# Relay_Board_Rev1-2_-_Altium.net
KiCad netlist of a schematic drawn in Altium Designer
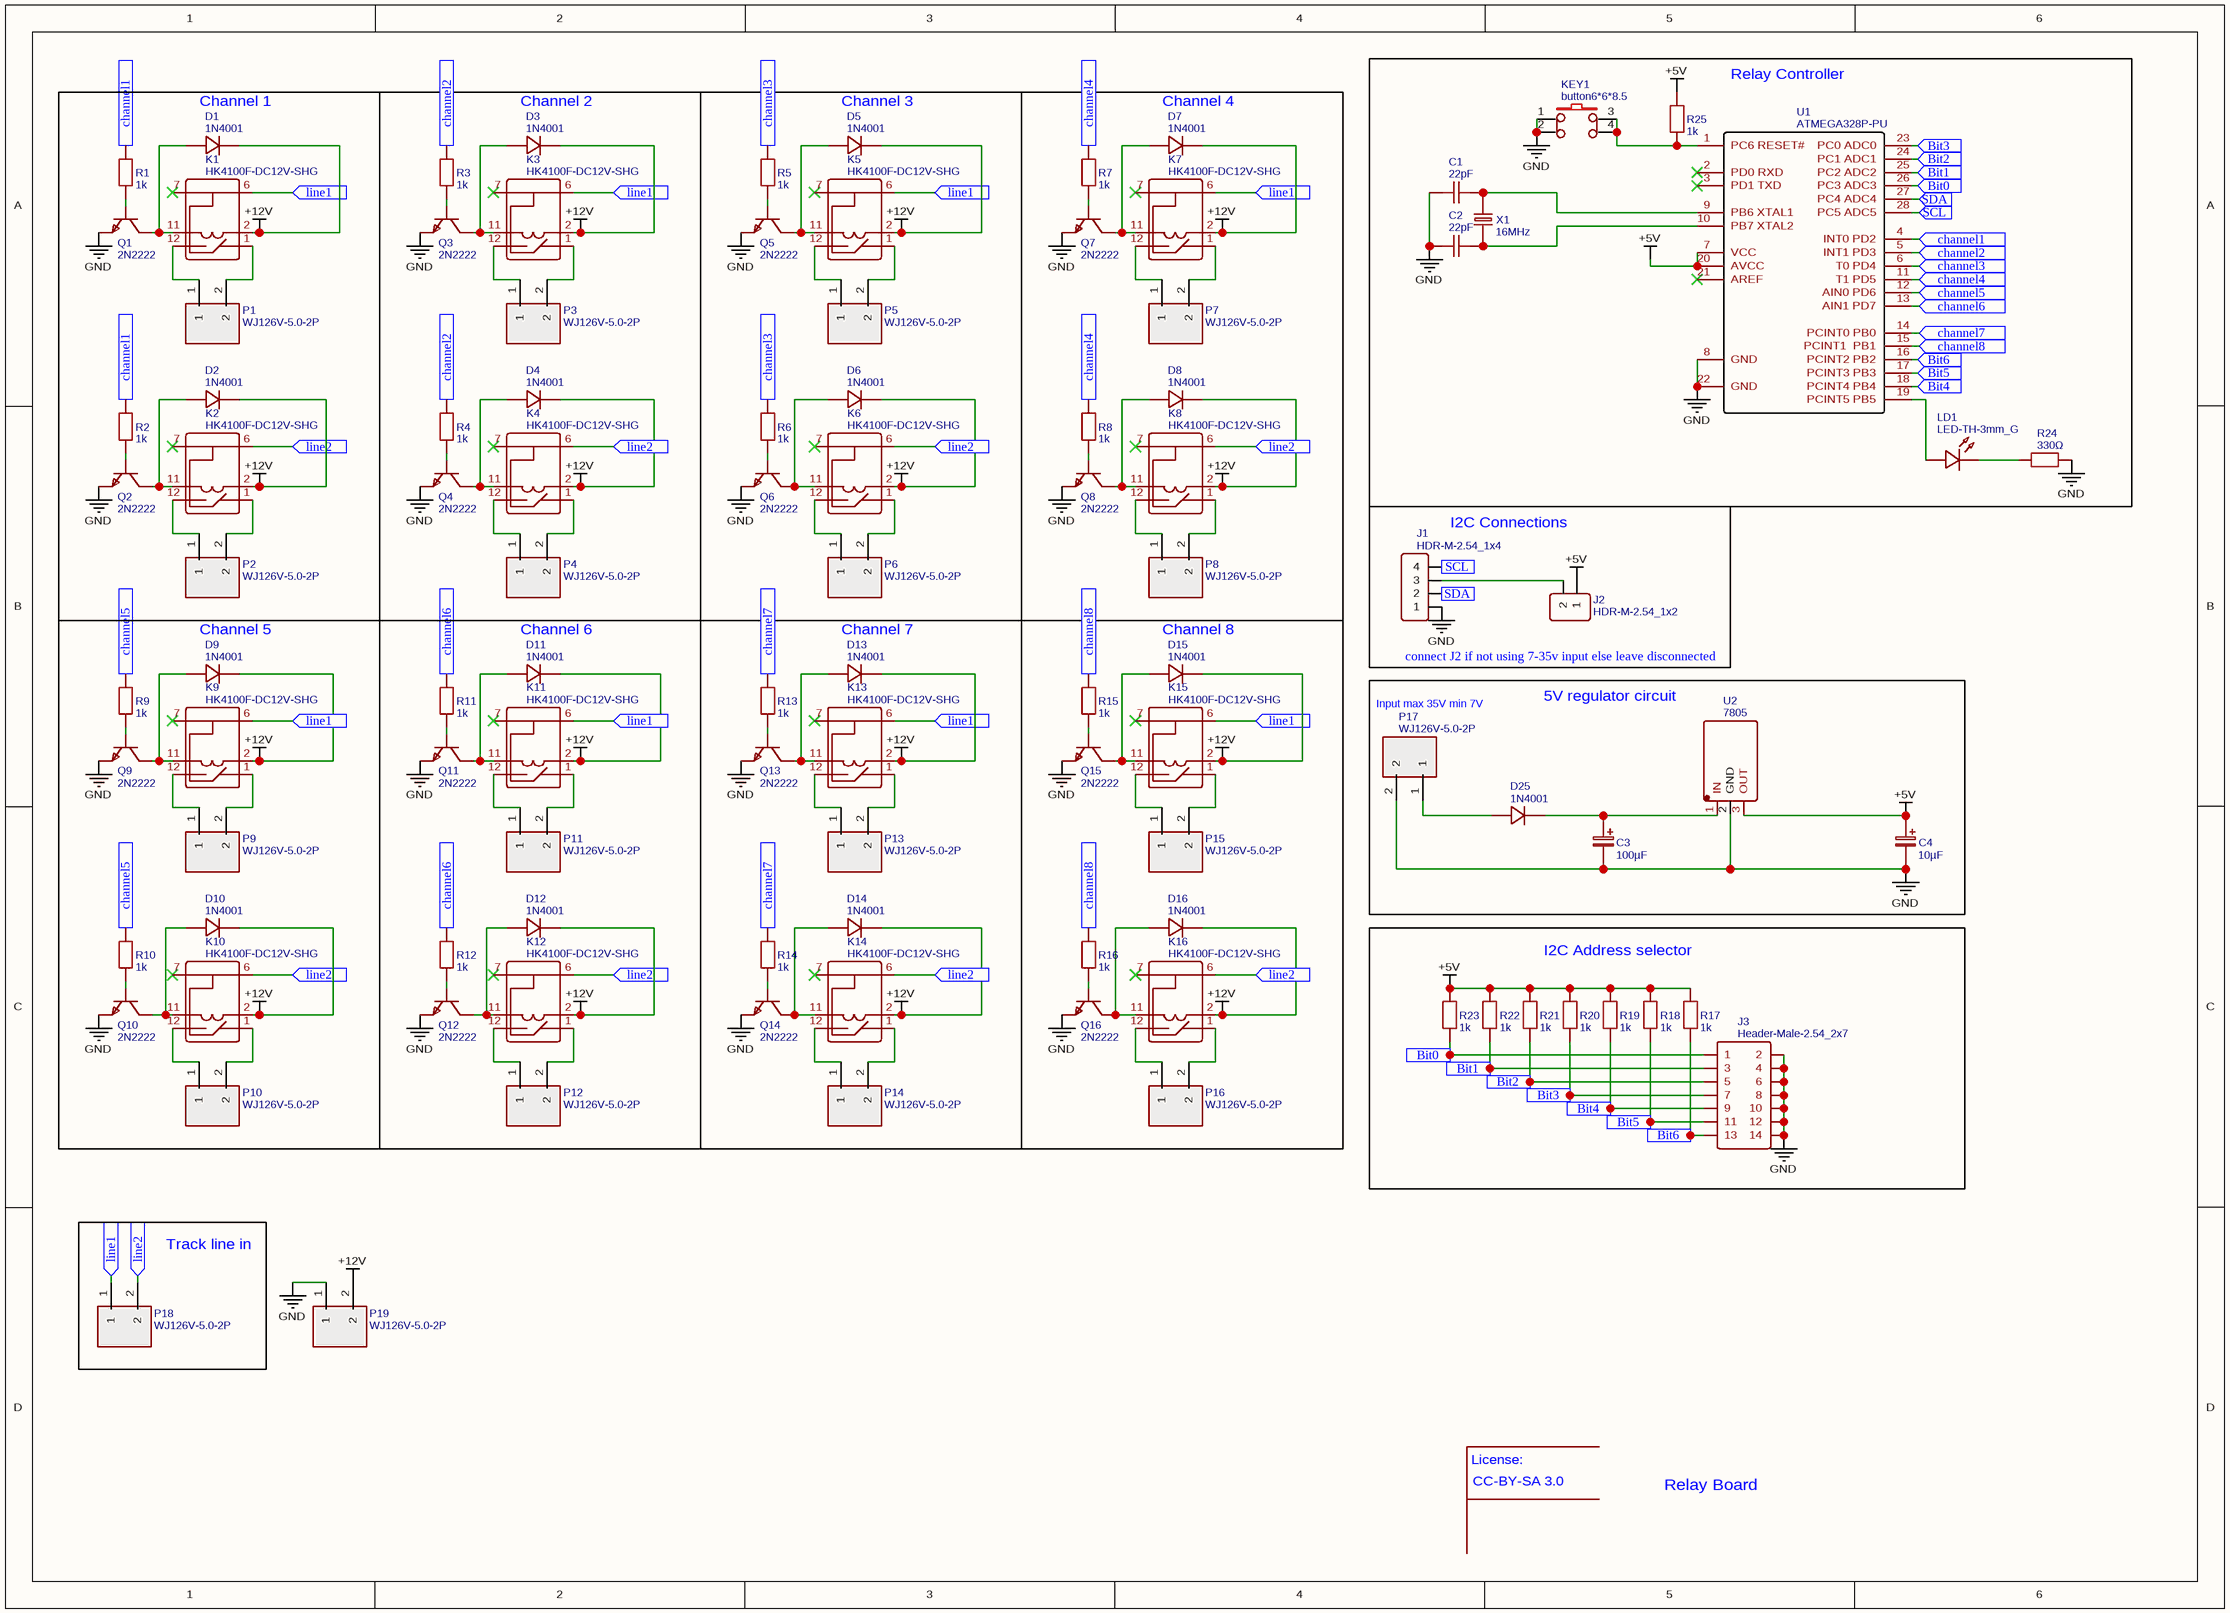
[diagram p0: Relay Board_Rev1-2 - Altium.schdoc]

(export (version "E")
  (design (tool "Eeschema 10.0.6"))
  (components
    (comp (ref "C1")
      (value "22pF")
      (fields (field (name "CONTRIBUTOR") "LCEDA_Lib"))
      (libsource (lib "altium-import") (part "root_0_22pF_"))
    )
    (comp (ref "C2")
      (value "22pF")
      (fields (field (name "CONTRIBUTOR") "LCEDA_Lib"))
      (libsource (lib "altium-import") (part "root_0_22pF_"))
    )
    (comp (ref "C3")
      (value "100µF")
      (fields (field (name "CONTRIBUTOR") "LCEDA_Lib"))
      (libsource (lib "altium-import") (part "root_3_100µF_"))
    )
    (comp (ref "C4")
      (value "10µF")
      (fields (field (name "CONTRIBUTOR") "LCEDA_Lib"))
      (libsource (lib "altium-import") (part "root_3_10µF_"))
    )
    (comp (ref "D1")
      (value "1N4001")
      (fields (field (name "BOM_SUPPLIER PART") "C82804"))
      (libsource (lib "altium-import") (part "root_2_1N4001_"))
    )
    (comp (ref "D2")
      (value "1N4001")
      (fields (field (name "BOM_SUPPLIER PART") "C82804"))
      (libsource (lib "altium-import") (part "root_2_1N4001_"))
    )
    (comp (ref "D3")
      (value "1N4001")
      (fields (field (name "BOM_SUPPLIER PART") "C82804"))
      (libsource (lib "altium-import") (part "root_2_1N4001_"))
    )
    (comp (ref "D4")
      (value "1N4001")
      (fields (field (name "BOM_SUPPLIER PART") "C82804"))
      (libsource (lib "altium-import") (part "root_2_1N4001_"))
    )
    (comp (ref "D5")
      (value "1N4001")
      (fields (field (name "BOM_SUPPLIER PART") "C82804"))
      (libsource (lib "altium-import") (part "root_2_1N4001_"))
    )
    (comp (ref "D6")
      (value "1N4001")
      (fields (field (name "BOM_SUPPLIER PART") "C82804"))
      (libsource (lib "altium-import") (part "root_2_1N4001_"))
    )
    (comp (ref "D7")
      (value "1N4001")
      (fields (field (name "BOM_SUPPLIER PART") "C82804"))
      (libsource (lib "altium-import") (part "root_2_1N4001_"))
    )
    (comp (ref "D8")
      (value "1N4001")
      (fields (field (name "BOM_SUPPLIER PART") "C82804"))
      (libsource (lib "altium-import") (part "root_2_1N4001_"))
    )
    (comp (ref "D9")
      (value "1N4001")
      (fields (field (name "BOM_SUPPLIER PART") "C82804"))
      (libsource (lib "altium-import") (part "root_2_1N4001_"))
    )
    (comp (ref "D10")
      (value "1N4001")
      (fields (field (name "BOM_SUPPLIER PART") "C82804"))
      (libsource (lib "altium-import") (part "root_2_1N4001_"))
    )
    (comp (ref "D11")
      (value "1N4001")
      (fields (field (name "BOM_SUPPLIER PART") "C82804"))
      (libsource (lib "altium-import") (part "root_2_1N4001_"))
    )
    (comp (ref "D12")
      (value "1N4001")
      (fields (field (name "BOM_SUPPLIER PART") "C82804"))
      (libsource (lib "altium-import") (part "root_2_1N4001_"))
    )
    (comp (ref "D13")
      (value "1N4001")
      (fields (field (name "BOM_SUPPLIER PART") "C82804"))
      (libsource (lib "altium-import") (part "root_2_1N4001_"))
    )
    (comp (ref "D14")
      (value "1N4001")
      (fields (field (name "BOM_SUPPLIER PART") "C82804"))
      (libsource (lib "altium-import") (part "root_2_1N4001_"))
    )
    (comp (ref "D15")
      (value "1N4001")
      (fields (field (name "BOM_SUPPLIER PART") "C82804"))
      (libsource (lib "altium-import") (part "root_2_1N4001_"))
    )
    (comp (ref "D16")
      (value "1N4001")
      (fields (field (name "BOM_SUPPLIER PART") "C82804"))
      (libsource (lib "altium-import") (part "root_2_1N4001_"))
    )
    (comp (ref "D25")
      (value "1N4001")
      (fields (field (name "BOM_SUPPLIER PART") "C82804"))
      (libsource (lib "altium-import") (part "root_2_1N4001_"))
    )
    (comp (ref "J1")
      (value "HDR-M-2.54_1x4")
      (fields (field (name "BOM_SUPPLIER PART") "C124378") (field (name "CONTRIBUTOR") "LCEDA_Lib"))
      (libsource (lib "altium-import") (part "root_2_HDR-M-2.54_1x4_"))
    )
    (comp (ref "J2")
      (value "HDR-M-2.54_1x2")
      (fields (field (name "BOM_SUPPLIER PART") "C124375") (field (name "CONTRIBUTOR") "LCEDA_Lib"))
      (libsource (lib "altium-import") (part "root_3_HDR-M-2.54_1x2_"))
    )
    (comp (ref "J3")
      (value "Header-Male-2.54_2x7")
      (fields
        (field (name "BOM_MANUFACTURER PART") "Double row of needle2X7P 2.54mm")
        (field (name "BOM_SUPPLIER PART") "C71397")
      )
      (libsource (lib "altium-import") (part "root_0_Header-Male-2.54_2x7_"))
    )
    (comp (ref "K1")
      (value "HK4100F-DC12V-SHG")
      (fields (field (name "BOM_SUPPLIER PART") "C13467"))
      (libsource (lib "altium-import") (part "root_1_HK4100F-DC12V-SHG_"))
    )
    (comp (ref "K2")
      (value "HK4100F-DC12V-SHG")
      (fields (field (name "BOM_SUPPLIER PART") "C13467"))
      (libsource (lib "altium-import") (part "root_1_HK4100F-DC12V-SHG_"))
    )
    (comp (ref "K3")
      (value "HK4100F-DC12V-SHG")
      (fields (field (name "BOM_SUPPLIER PART") "C13467"))
      (libsource (lib "altium-import") (part "root_1_HK4100F-DC12V-SHG_"))
    )
    (comp (ref "K4")
      (value "HK4100F-DC12V-SHG")
      (fields (field (name "BOM_SUPPLIER PART") "C13467"))
      (libsource (lib "altium-import") (part "root_1_HK4100F-DC12V-SHG_"))
    )
    (comp (ref "K5")
      (value "HK4100F-DC12V-SHG")
      (fields (field (name "BOM_SUPPLIER PART") "C13467"))
      (libsource (lib "altium-import") (part "root_1_HK4100F-DC12V-SHG_"))
    )
    (comp (ref "K6")
      (value "HK4100F-DC12V-SHG")
      (fields (field (name "BOM_SUPPLIER PART") "C13467"))
      (libsource (lib "altium-import") (part "root_1_HK4100F-DC12V-SHG_"))
    )
    (comp (ref "K7")
      (value "HK4100F-DC12V-SHG")
      (fields (field (name "BOM_SUPPLIER PART") "C13467"))
      (libsource (lib "altium-import") (part "root_1_HK4100F-DC12V-SHG_"))
    )
    (comp (ref "K8")
      (value "HK4100F-DC12V-SHG")
      (fields (field (name "BOM_SUPPLIER PART") "C13467"))
      (libsource (lib "altium-import") (part "root_1_HK4100F-DC12V-SHG_"))
    )
    (comp (ref "K9")
      (value "HK4100F-DC12V-SHG")
      (fields (field (name "BOM_SUPPLIER PART") "C13467"))
      (libsource (lib "altium-import") (part "root_1_HK4100F-DC12V-SHG_"))
    )
    (comp (ref "K10")
      (value "HK4100F-DC12V-SHG")
      (fields (field (name "BOM_SUPPLIER PART") "C13467"))
      (libsource (lib "altium-import") (part "root_1_HK4100F-DC12V-SHG_"))
    )
    (comp (ref "K11")
      (value "HK4100F-DC12V-SHG")
      (fields (field (name "BOM_SUPPLIER PART") "C13467"))
      (libsource (lib "altium-import") (part "root_1_HK4100F-DC12V-SHG_"))
    )
    (comp (ref "K12")
      (value "HK4100F-DC12V-SHG")
      (fields (field (name "BOM_SUPPLIER PART") "C13467"))
      (libsource (lib "altium-import") (part "root_1_HK4100F-DC12V-SHG_"))
    )
    (comp (ref "K13")
      (value "HK4100F-DC12V-SHG")
      (fields (field (name "BOM_SUPPLIER PART") "C13467"))
      (libsource (lib "altium-import") (part "root_1_HK4100F-DC12V-SHG_"))
    )
    (comp (ref "K14")
      (value "HK4100F-DC12V-SHG")
      (fields (field (name "BOM_SUPPLIER PART") "C13467"))
      (libsource (lib "altium-import") (part "root_1_HK4100F-DC12V-SHG_"))
    )
    (comp (ref "K15")
      (value "HK4100F-DC12V-SHG")
      (fields (field (name "BOM_SUPPLIER PART") "C13467"))
      (libsource (lib "altium-import") (part "root_1_HK4100F-DC12V-SHG_"))
    )
    (comp (ref "K16")
      (value "HK4100F-DC12V-SHG")
      (fields (field (name "BOM_SUPPLIER PART") "C13467"))
      (libsource (lib "altium-import") (part "root_1_HK4100F-DC12V-SHG_"))
    )
    (comp (ref "KEY1")
      (value "button6*6*8.5")
      (fields (field (name "BOM_SUPPLIER PART") "C59980"))
      (libsource (lib "altium-import") (part "root_0_button6*6*8.5_"))
    )
    (comp (ref "LD1")
      (value "LED-TH-3mm_G")
      (fields
        (field (name "BOM_MANUFACTURER PART") "204-10SYGD/S530-E3")
        (field (name "BOM_SUPPLIER PART") "C85161")
        (field (name "CONTRIBUTOR") "LCEDA_Lib")
      )
      (libsource (lib "altium-import") (part "root_0_LED-TH-3mm_G_"))
    )
    (comp (ref "P1")
      (value "WJ126V-5.0-2P")
      (fields (field (name "BOM_SUPPLIER PART") "C8404"))
      (libsource (lib "altium-import") (part "root_1_WJ126V-5.0-2P_"))
    )
    (comp (ref "P2")
      (value "WJ126V-5.0-2P")
      (fields (field (name "BOM_SUPPLIER PART") "C8404"))
      (libsource (lib "altium-import") (part "root_1_WJ126V-5.0-2P_"))
    )
    (comp (ref "P3")
      (value "WJ126V-5.0-2P")
      (fields (field (name "BOM_SUPPLIER PART") "C8404"))
      (libsource (lib "altium-import") (part "root_1_WJ126V-5.0-2P_"))
    )
    (comp (ref "P4")
      (value "WJ126V-5.0-2P")
      (fields (field (name "BOM_SUPPLIER PART") "C8404"))
      (libsource (lib "altium-import") (part "root_1_WJ126V-5.0-2P_"))
    )
    (comp (ref "P5")
      (value "WJ126V-5.0-2P")
      (fields (field (name "BOM_SUPPLIER PART") "C8404"))
      (libsource (lib "altium-import") (part "root_1_WJ126V-5.0-2P_"))
    )
    (comp (ref "P6")
      (value "WJ126V-5.0-2P")
      (fields (field (name "BOM_SUPPLIER PART") "C8404"))
      (libsource (lib "altium-import") (part "root_1_WJ126V-5.0-2P_"))
    )
    (comp (ref "P7")
      (value "WJ126V-5.0-2P")
      (fields (field (name "BOM_SUPPLIER PART") "C8404"))
      (libsource (lib "altium-import") (part "root_1_WJ126V-5.0-2P_"))
    )
    (comp (ref "P8")
      (value "WJ126V-5.0-2P")
      (fields (field (name "BOM_SUPPLIER PART") "C8404"))
      (libsource (lib "altium-import") (part "root_1_WJ126V-5.0-2P_"))
    )
    (comp (ref "P9")
      (value "WJ126V-5.0-2P")
      (fields (field (name "BOM_SUPPLIER PART") "C8404"))
      (libsource (lib "altium-import") (part "root_1_WJ126V-5.0-2P_"))
    )
    (comp (ref "P10")
      (value "WJ126V-5.0-2P")
      (fields (field (name "BOM_SUPPLIER PART") "C8404"))
      (libsource (lib "altium-import") (part "root_1_WJ126V-5.0-2P_"))
    )
    (comp (ref "P11")
      (value "WJ126V-5.0-2P")
      (fields (field (name "BOM_SUPPLIER PART") "C8404"))
      (libsource (lib "altium-import") (part "root_1_WJ126V-5.0-2P_"))
    )
    (comp (ref "P12")
      (value "WJ126V-5.0-2P")
      (fields (field (name "BOM_SUPPLIER PART") "C8404"))
      (libsource (lib "altium-import") (part "root_1_WJ126V-5.0-2P_"))
    )
    (comp (ref "P13")
      (value "WJ126V-5.0-2P")
      (fields (field (name "BOM_SUPPLIER PART") "C8404"))
      (libsource (lib "altium-import") (part "root_1_WJ126V-5.0-2P_"))
    )
    (comp (ref "P14")
      (value "WJ126V-5.0-2P")
      (fields (field (name "BOM_SUPPLIER PART") "C8404"))
      (libsource (lib "altium-import") (part "root_1_WJ126V-5.0-2P_"))
    )
    (comp (ref "P15")
      (value "WJ126V-5.0-2P")
      (fields (field (name "BOM_SUPPLIER PART") "C8404"))
      (libsource (lib "altium-import") (part "root_1_WJ126V-5.0-2P_"))
    )
    (comp (ref "P16")
      (value "WJ126V-5.0-2P")
      (fields (field (name "BOM_SUPPLIER PART") "C8404"))
      (libsource (lib "altium-import") (part "root_1_WJ126V-5.0-2P_"))
    )
    (comp (ref "P17")
      (value "WJ126V-5.0-2P")
      (fields (field (name "BOM_SUPPLIER PART") "C8404"))
      (libsource (lib "altium-import") (part "root_3_WJ126V-5.0-2P_"))
    )
    (comp (ref "P18")
      (value "WJ126V-5.0-2P")
      (fields (field (name "BOM_SUPPLIER PART") "C8404"))
      (libsource (lib "altium-import") (part "root_1_WJ126V-5.0-2P_"))
    )
    (comp (ref "P19")
      (value "WJ126V-5.0-2P")
      (fields (field (name "BOM_SUPPLIER PART") "C8404"))
      (libsource (lib "altium-import") (part "root_1_WJ126V-5.0-2P_"))
    )
    (comp (ref "Q1")
      (value "2N2222")
      (fields (field (name "BOM_SUPPLIER PART") "C118536") (field (name "CONTRIBUTOR") "LCSC"))
      (libsource (lib "altium-import") (part "root_3_2N2222_"))
    )
    (comp (ref "Q2")
      (value "2N2222")
      (fields (field (name "BOM_SUPPLIER PART") "C118536") (field (name "CONTRIBUTOR") "LCSC"))
      (libsource (lib "altium-import") (part "root_3_2N2222_"))
    )
    (comp (ref "Q3")
      (value "2N2222")
      (fields (field (name "BOM_SUPPLIER PART") "C118536") (field (name "CONTRIBUTOR") "LCSC"))
      (libsource (lib "altium-import") (part "root_3_2N2222_"))
    )
    (comp (ref "Q4")
      (value "2N2222")
      (fields (field (name "BOM_SUPPLIER PART") "C118536") (field (name "CONTRIBUTOR") "LCSC"))
      (libsource (lib "altium-import") (part "root_3_2N2222_"))
    )
    (comp (ref "Q5")
      (value "2N2222")
      (fields (field (name "BOM_SUPPLIER PART") "C118536") (field (name "CONTRIBUTOR") "LCSC"))
      (libsource (lib "altium-import") (part "root_3_2N2222_"))
    )
    (comp (ref "Q6")
      (value "2N2222")
      (fields (field (name "BOM_SUPPLIER PART") "C118536") (field (name "CONTRIBUTOR") "LCSC"))
      (libsource (lib "altium-import") (part "root_3_2N2222_"))
    )
    (comp (ref "Q7")
      (value "2N2222")
      (fields (field (name "BOM_SUPPLIER PART") "C118536") (field (name "CONTRIBUTOR") "LCSC"))
      (libsource (lib "altium-import") (part "root_3_2N2222_"))
    )
    (comp (ref "Q8")
      (value "2N2222")
      (fields (field (name "BOM_SUPPLIER PART") "C118536") (field (name "CONTRIBUTOR") "LCSC"))
      (libsource (lib "altium-import") (part "root_3_2N2222_"))
    )
    (comp (ref "Q9")
      (value "2N2222")
      (fields (field (name "BOM_SUPPLIER PART") "C118536") (field (name "CONTRIBUTOR") "LCSC"))
      (libsource (lib "altium-import") (part "root_3_2N2222_"))
    )
    (comp (ref "Q10")
      (value "2N2222")
      (fields (field (name "BOM_SUPPLIER PART") "C118536") (field (name "CONTRIBUTOR") "LCSC"))
      (libsource (lib "altium-import") (part "root_3_2N2222_"))
    )
    (comp (ref "Q11")
      (value "2N2222")
      (fields (field (name "BOM_SUPPLIER PART") "C118536") (field (name "CONTRIBUTOR") "LCSC"))
      (libsource (lib "altium-import") (part "root_3_2N2222_"))
    )
    (comp (ref "Q12")
      (value "2N2222")
      (fields (field (name "BOM_SUPPLIER PART") "C118536") (field (name "CONTRIBUTOR") "LCSC"))
      (libsource (lib "altium-import") (part "root_3_2N2222_"))
    )
    (comp (ref "Q13")
      (value "2N2222")
      (fields (field (name "BOM_SUPPLIER PART") "C118536") (field (name "CONTRIBUTOR") "LCSC"))
      (libsource (lib "altium-import") (part "root_3_2N2222_"))
    )
    (comp (ref "Q14")
      (value "2N2222")
      (fields (field (name "BOM_SUPPLIER PART") "C118536") (field (name "CONTRIBUTOR") "LCSC"))
      (libsource (lib "altium-import") (part "root_3_2N2222_"))
    )
    (comp (ref "Q15")
      (value "2N2222")
      (fields (field (name "BOM_SUPPLIER PART") "C118536") (field (name "CONTRIBUTOR") "LCSC"))
      (libsource (lib "altium-import") (part "root_3_2N2222_"))
    )
    (comp (ref "Q16")
      (value "2N2222")
      (fields (field (name "BOM_SUPPLIER PART") "C118536") (field (name "CONTRIBUTOR") "LCSC"))
      (libsource (lib "altium-import") (part "root_3_2N2222_"))
    )
    (comp (ref "R1")
      (value "1k")
      (fields (field (name "CONTRIBUTOR") "LCEDA_Lib"))
      (libsource (lib "altium-import") (part "root_1_1k_"))
    )
    (comp (ref "R2")
      (value "1k")
      (fields (field (name "CONTRIBUTOR") "LCEDA_Lib"))
      (libsource (lib "altium-import") (part "root_1_1k_"))
    )
    (comp (ref "R3")
      (value "1k")
      (fields (field (name "CONTRIBUTOR") "LCEDA_Lib"))
      (libsource (lib "altium-import") (part "root_1_1k_"))
    )
    (comp (ref "R4")
      (value "1k")
      (fields (field (name "CONTRIBUTOR") "LCEDA_Lib"))
      (libsource (lib "altium-import") (part "root_1_1k_"))
    )
    (comp (ref "R5")
      (value "1k")
      (fields (field (name "CONTRIBUTOR") "LCEDA_Lib"))
      (libsource (lib "altium-import") (part "root_1_1k_"))
    )
    (comp (ref "R6")
      (value "1k")
      (fields (field (name "CONTRIBUTOR") "LCEDA_Lib"))
      (libsource (lib "altium-import") (part "root_1_1k_"))
    )
    (comp (ref "R7")
      (value "1k")
      (fields (field (name "CONTRIBUTOR") "LCEDA_Lib"))
      (libsource (lib "altium-import") (part "root_1_1k_"))
    )
    (comp (ref "R8")
      (value "1k")
      (fields (field (name "CONTRIBUTOR") "LCEDA_Lib"))
      (libsource (lib "altium-import") (part "root_1_1k_"))
    )
    (comp (ref "R9")
      (value "1k")
      (fields (field (name "CONTRIBUTOR") "LCEDA_Lib"))
      (libsource (lib "altium-import") (part "root_1_1k_"))
    )
    (comp (ref "R10")
      (value "1k")
      (fields (field (name "CONTRIBUTOR") "LCEDA_Lib"))
      (libsource (lib "altium-import") (part "root_1_1k_"))
    )
    (comp (ref "R11")
      (value "1k")
      (fields (field (name "CONTRIBUTOR") "LCEDA_Lib"))
      (libsource (lib "altium-import") (part "root_1_1k_"))
    )
    (comp (ref "R12")
      (value "1k")
      (fields (field (name "CONTRIBUTOR") "LCEDA_Lib"))
      (libsource (lib "altium-import") (part "root_1_1k_"))
    )
    (comp (ref "R13")
      (value "1k")
      (fields (field (name "CONTRIBUTOR") "LCEDA_Lib"))
      (libsource (lib "altium-import") (part "root_1_1k_"))
    )
    (comp (ref "R14")
      (value "1k")
      (fields (field (name "CONTRIBUTOR") "LCEDA_Lib"))
      (libsource (lib "altium-import") (part "root_1_1k_"))
    )
    (comp (ref "R15")
      (value "1k")
      (fields (field (name "CONTRIBUTOR") "LCEDA_Lib"))
      (libsource (lib "altium-import") (part "root_1_1k_"))
    )
    (comp (ref "R16")
      (value "1k")
      (fields (field (name "CONTRIBUTOR") "LCEDA_Lib"))
      (libsource (lib "altium-import") (part "root_1_1k_"))
    )
    (comp (ref "R17")
      (value "1k")
      (fields (field (name "CONTRIBUTOR") "LCEDA_Lib"))
      (libsource (lib "altium-import") (part "root_1_1k_"))
    )
    (comp (ref "R18")
      (value "1k")
      (fields (field (name "CONTRIBUTOR") "LCEDA_Lib"))
      (libsource (lib "altium-import") (part "root_1_1k_"))
    )
    (comp (ref "R19")
      (value "1k")
      (fields (field (name "CONTRIBUTOR") "LCEDA_Lib"))
      (libsource (lib "altium-import") (part "root_1_1k_"))
    )
    (comp (ref "R20")
      (value "1k")
      (fields (field (name "CONTRIBUTOR") "LCEDA_Lib"))
      (libsource (lib "altium-import") (part "root_1_1k_"))
    )
    (comp (ref "R21")
      (value "1k")
      (fields (field (name "CONTRIBUTOR") "LCEDA_Lib"))
      (libsource (lib "altium-import") (part "root_1_1k_"))
    )
    (comp (ref "R22")
      (value "1k")
      (fields (field (name "CONTRIBUTOR") "LCEDA_Lib"))
      (libsource (lib "altium-import") (part "root_1_1k_"))
    )
    (comp (ref "R23")
      (value "1k")
      (fields (field (name "CONTRIBUTOR") "LCEDA_Lib"))
      (libsource (lib "altium-import") (part "root_1_1k_"))
    )
    (comp (ref "R24")
      (value "330Ω")
      (fields (field (name "CONTRIBUTOR") "LCEDA_Lib"))
      (libsource (lib "altium-import") (part "root_0_330Ω_"))
    )
    (comp (ref "R25")
      (value "1k")
      (fields (field (name "CONTRIBUTOR") "LCEDA_Lib"))
      (libsource (lib "altium-import") (part "root_1_1k_"))
    )
    (comp (ref "U1")
      (value "ATMEGA328P-PU")
      (fields (field (name "BOM_SUPPLIER PART") "C33901") (field (name "CONTRIBUTOR") "LCSC"))
      (libsource (lib "altium-import") (part "root_0_ATMEGA328P-PU_"))
    )
    (comp (ref "U2")
      (value "7805")
      (fields (field (name "BOM_SUPPLIER PART") "C305416") (field (name "CONTRIBUTOR") "LCSC"))
      (libsource (lib "altium-import") (part "root_1_7805_"))
    )
    (comp (ref "X1")
      (value "16MHz")
      (fields
        (field (name "BOM_SUPPLIER PART") "C295075")
        (field (name "BOM_MANUFACTURER PART") "XIHCELNANF-16MHZ")
        (field (name "CONTRIBUTOR") "LCSC")
      )
      (libsource (lib "altium-import") (part "root_3_16MHz_"))
    )
  )
  (nets
    (net (code "1") (name "+5V") (class "Default")
      (node (ref "C4") (pin "1") (pinfunction "1_1") (pintype "passive"))
      (node (ref "J2") (pin "1") (pinfunction "1_1") (pintype "passive"))
      (node (ref "R17") (pin "2") (pinfunction "2_2") (pintype "passive"))
      (node (ref "R18") (pin "2") (pinfunction "2_2") (pintype "passive"))
      (node (ref "R19") (pin "2") (pinfunction "2_2") (pintype "passive"))
      (node (ref "R20") (pin "2") (pinfunction "2_2") (pintype "passive"))
      (node (ref "R21") (pin "2") (pinfunction "2_2") (pintype "passive"))
      (node (ref "R22") (pin "2") (pinfunction "2_2") (pintype "passive"))
      (node (ref "R23") (pin "2") (pinfunction "2_2") (pintype "passive"))
      (node (ref "R25") (pin "2") (pinfunction "2_2") (pintype "passive"))
      (node (ref "U1") (pin "20") (pinfunction "AVCC_20") (pintype "passive"))
      (node (ref "U1") (pin "7") (pinfunction "VCC_7") (pintype "passive"))
      (node (ref "U2") (pin "3") (pinfunction "OUT_3") (pintype "passive"))
    )
    (net (code "2") (name "+12V") (class "Default")
      (node (ref "D1") (pin "1") (pinfunction "K_1") (pintype "passive"))
      (node (ref "D10") (pin "1") (pinfunction "K_1") (pintype "passive"))
      (node (ref "D11") (pin "1") (pinfunction "K_1") (pintype "passive"))
      (node (ref "D12") (pin "1") (pinfunction "K_1") (pintype "passive"))
      (node (ref "D13") (pin "1") (pinfunction "K_1") (pintype "passive"))
      (node (ref "D14") (pin "1") (pinfunction "K_1") (pintype "passive"))
      (node (ref "D15") (pin "1") (pinfunction "K_1") (pintype "passive"))
      (node (ref "D16") (pin "1") (pinfunction "K_1") (pintype "passive"))
      (node (ref "D2") (pin "1") (pinfunction "K_1") (pintype "passive"))
      (node (ref "D3") (pin "1") (pinfunction "K_1") (pintype "passive"))
      (node (ref "D4") (pin "1") (pinfunction "K_1") (pintype "passive"))
      (node (ref "D5") (pin "1") (pinfunction "K_1") (pintype "passive"))
      (node (ref "D6") (pin "1") (pinfunction "K_1") (pintype "passive"))
      (node (ref "D7") (pin "1") (pinfunction "K_1") (pintype "passive"))
      (node (ref "D8") (pin "1") (pinfunction "K_1") (pintype "passive"))
      (node (ref "D9") (pin "1") (pinfunction "K_1") (pintype "passive"))
      (node (ref "K1") (pin "2") (pinfunction "2_2") (pintype "passive"))
      (node (ref "K10") (pin "2") (pinfunction "2_2") (pintype "passive"))
      (node (ref "K11") (pin "2") (pinfunction "2_2") (pintype "passive"))
      (node (ref "K12") (pin "2") (pinfunction "2_2") (pintype "passive"))
      (node (ref "K13") (pin "2") (pinfunction "2_2") (pintype "passive"))
      (node (ref "K14") (pin "2") (pinfunction "2_2") (pintype "passive"))
      (node (ref "K15") (pin "2") (pinfunction "2_2") (pintype "passive"))
      (node (ref "K16") (pin "2") (pinfunction "2_2") (pintype "passive"))
      (node (ref "K2") (pin "2") (pinfunction "2_2") (pintype "passive"))
      (node (ref "K3") (pin "2") (pinfunction "2_2") (pintype "passive"))
      (node (ref "K4") (pin "2") (pinfunction "2_2") (pintype "passive"))
      (node (ref "K5") (pin "2") (pinfunction "2_2") (pintype "passive"))
      (node (ref "K6") (pin "2") (pinfunction "2_2") (pintype "passive"))
      (node (ref "K7") (pin "2") (pinfunction "2_2") (pintype "passive"))
      (node (ref "K8") (pin "2") (pinfunction "2_2") (pintype "passive"))
      (node (ref "K9") (pin "2") (pinfunction "2_2") (pintype "passive"))
      (node (ref "P19") (pin "2") (pinfunction "2_2") (pintype "passive"))
    )
    (net (code "3") (name "/Bit0") (class "Default")
      (node (ref "J3") (pin "1") (pinfunction "1_1") (pintype "passive"))
      (node (ref "R23") (pin "1") (pinfunction "1_1") (pintype "passive"))
      (node (ref "U1") (pin "26") (pinfunction "PC3_ADC3_26") (pintype "passive"))
    )
    (net (code "4") (name "/Bit1") (class "Default")
      (node (ref "J3") (pin "3") (pinfunction "3_3") (pintype "passive"))
      (node (ref "R22") (pin "1") (pinfunction "1_1") (pintype "passive"))
      (node (ref "U1") (pin "25") (pinfunction "PC2_ADC2_25") (pintype "passive"))
    )
    (net (code "5") (name "/Bit2") (class "Default")
      (node (ref "J3") (pin "5") (pinfunction "5_5") (pintype "passive"))
      (node (ref "R21") (pin "1") (pinfunction "1_1") (pintype "passive"))
      (node (ref "U1") (pin "24") (pinfunction "PC1_ADC1_24") (pintype "passive"))
    )
    (net (code "6") (name "/Bit3") (class "Default")
      (node (ref "J3") (pin "7") (pinfunction "7_7") (pintype "passive"))
      (node (ref "R20") (pin "1") (pinfunction "1_1") (pintype "passive"))
      (node (ref "U1") (pin "23") (pinfunction "PC0_ADC0_23") (pintype "passive"))
    )
    (net (code "7") (name "/Bit4") (class "Default")
      (node (ref "J3") (pin "9") (pinfunction "9_9") (pintype "passive"))
      (node (ref "R19") (pin "1") (pinfunction "1_1") (pintype "passive"))
      (node (ref "U1") (pin "18") (pinfunction "PCINT4_PB4_18") (pintype "passive"))
    )
    (net (code "8") (name "/Bit5") (class "Default")
      (node (ref "J3") (pin "11") (pinfunction "11_11") (pintype "passive"))
      (node (ref "R18") (pin "1") (pinfunction "1_1") (pintype "passive"))
      (node (ref "U1") (pin "17") (pinfunction "PCINT3_PB3_17") (pintype "passive"))
    )
    (net (code "9") (name "/Bit6") (class "Default")
      (node (ref "J3") (pin "13") (pinfunction "13_13") (pintype "passive"))
      (node (ref "R17") (pin "1") (pinfunction "1_1") (pintype "passive"))
      (node (ref "U1") (pin "16") (pinfunction "PCINT2_PB2_16") (pintype "passive"))
    )
    (net (code "10") (name "/SCL") (class "Default")
      (node (ref "J1") (pin "4") (pinfunction "4_4") (pintype "passive"))
      (node (ref "U1") (pin "28") (pinfunction "PC5_ADC5_28") (pintype "passive"))
    )
    (net (code "11") (name "/SDA") (class "Default")
      (node (ref "J1") (pin "2") (pinfunction "2_2") (pintype "passive"))
      (node (ref "U1") (pin "27") (pinfunction "PC4_ADC4_27") (pintype "passive"))
    )
    (net (code "12") (name "/channel1") (class "Default")
      (node (ref "R1") (pin "2") (pinfunction "2_2") (pintype "passive"))
      (node (ref "R2") (pin "2") (pinfunction "2_2") (pintype "passive"))
      (node (ref "U1") (pin "4") (pinfunction "INT0_PD2_4") (pintype "passive"))
    )
    (net (code "13") (name "/channel2") (class "Default")
      (node (ref "R3") (pin "2") (pinfunction "2_2") (pintype "passive"))
      (node (ref "R4") (pin "2") (pinfunction "2_2") (pintype "passive"))
      (node (ref "U1") (pin "5") (pinfunction "INT1_PD3_5") (pintype "passive"))
    )
    (net (code "14") (name "/channel3") (class "Default")
      (node (ref "R5") (pin "2") (pinfunction "2_2") (pintype "passive"))
      (node (ref "R6") (pin "2") (pinfunction "2_2") (pintype "passive"))
      (node (ref "U1") (pin "6") (pinfunction "T0_PD4_6") (pintype "passive"))
    )
    (net (code "15") (name "/channel4") (class "Default")
      (node (ref "R7") (pin "2") (pinfunction "2_2") (pintype "passive"))
      (node (ref "R8") (pin "2") (pinfunction "2_2") (pintype "passive"))
      (node (ref "U1") (pin "11") (pinfunction "T1_PD5_11") (pintype "passive"))
    )
    (net (code "16") (name "/channel5") (class "Default")
      (node (ref "R10") (pin "2") (pinfunction "2_2") (pintype "passive"))
      (node (ref "R9") (pin "2") (pinfunction "2_2") (pintype "passive"))
      (node (ref "U1") (pin "12") (pinfunction "AIN0_PD6_12") (pintype "passive"))
    )
    (net (code "17") (name "/channel6") (class "Default")
      (node (ref "R11") (pin "2") (pinfunction "2_2") (pintype "passive"))
      (node (ref "R12") (pin "2") (pinfunction "2_2") (pintype "passive"))
      (node (ref "U1") (pin "13") (pinfunction "AIN1_PD7_13") (pintype "passive"))
    )
    (net (code "18") (name "/channel7") (class "Default")
      (node (ref "R13") (pin "2") (pinfunction "2_2") (pintype "passive"))
      (node (ref "R14") (pin "2") (pinfunction "2_2") (pintype "passive"))
      (node (ref "U1") (pin "14") (pinfunction "PCINT0_PB0_14") (pintype "passive"))
    )
    (net (code "19") (name "/channel8") (class "Default")
      (node (ref "R15") (pin "2") (pinfunction "2_2") (pintype "passive"))
      (node (ref "R16") (pin "2") (pinfunction "2_2") (pintype "passive"))
      (node (ref "U1") (pin "15") (pinfunction "PCINT1__PB1_15") (pintype "passive"))
    )
    (net (code "20") (name "/line1") (class "Default")
      (node (ref "K1") (pin "6") (pinfunction "6_6") (pintype "passive"))
      (node (ref "K11") (pin "6") (pinfunction "6_6") (pintype "passive"))
      (node (ref "K13") (pin "6") (pinfunction "6_6") (pintype "passive"))
      (node (ref "K15") (pin "6") (pinfunction "6_6") (pintype "passive"))
      (node (ref "K3") (pin "6") (pinfunction "6_6") (pintype "passive"))
      (node (ref "K5") (pin "6") (pinfunction "6_6") (pintype "passive"))
      (node (ref "K7") (pin "6") (pinfunction "6_6") (pintype "passive"))
      (node (ref "K9") (pin "6") (pinfunction "6_6") (pintype "passive"))
      (node (ref "P18") (pin "1") (pinfunction "1_1") (pintype "passive"))
    )
    (net (code "21") (name "/line2") (class "Default")
      (node (ref "K10") (pin "6") (pinfunction "6_6") (pintype "passive"))
      (node (ref "K12") (pin "6") (pinfunction "6_6") (pintype "passive"))
      (node (ref "K14") (pin "6") (pinfunction "6_6") (pintype "passive"))
      (node (ref "K16") (pin "6") (pinfunction "6_6") (pintype "passive"))
      (node (ref "K2") (pin "6") (pinfunction "6_6") (pintype "passive"))
      (node (ref "K4") (pin "6") (pinfunction "6_6") (pintype "passive"))
      (node (ref "K6") (pin "6") (pinfunction "6_6") (pintype "passive"))
      (node (ref "K8") (pin "6") (pinfunction "6_6") (pintype "passive"))
      (node (ref "P18") (pin "2") (pinfunction "2_2") (pintype "passive"))
    )
    (net (code "22") (name "GND") (class "Default")
      (node (ref "C1") (pin "1") (pinfunction "1_1") (pintype "passive"))
      (node (ref "C2") (pin "1") (pinfunction "1_1") (pintype "passive"))
      (node (ref "C3") (pin "2") (pinfunction "2_2") (pintype "passive"))
      (node (ref "C4") (pin "2") (pinfunction "2_2") (pintype "passive"))
      (node (ref "J1") (pin "1") (pinfunction "1_1") (pintype "passive"))
      (node (ref "J3") (pin "10") (pinfunction "10_10") (pintype "passive"))
      (node (ref "J3") (pin "12") (pinfunction "12_12") (pintype "passive"))
      (node (ref "J3") (pin "14") (pinfunction "14_14") (pintype "passive"))
      (node (ref "J3") (pin "2") (pinfunction "2_2") (pintype "passive"))
      (node (ref "J3") (pin "4") (pinfunction "4_4") (pintype "passive"))
      (node (ref "J3") (pin "6") (pinfunction "6_6") (pintype "passive"))
      (node (ref "J3") (pin "8") (pinfunction "8_8") (pintype "passive"))
      (node (ref "KEY1") (pin "1") (pinfunction "1_1") (pintype "passive"))
      (node (ref "KEY1") (pin "2") (pinfunction "2_2") (pintype "passive"))
      (node (ref "P17") (pin "2") (pinfunction "2_2") (pintype "passive"))
      (node (ref "P19") (pin "1") (pinfunction "1_1") (pintype "passive"))
      (node (ref "Q1") (pin "1") (pinfunction "E_1") (pintype "passive"))
      (node (ref "Q10") (pin "1") (pinfunction "E_1") (pintype "passive"))
      (node (ref "Q11") (pin "1") (pinfunction "E_1") (pintype "passive"))
      (node (ref "Q12") (pin "1") (pinfunction "E_1") (pintype "passive"))
      (node (ref "Q13") (pin "1") (pinfunction "E_1") (pintype "passive"))
      (node (ref "Q14") (pin "1") (pinfunction "E_1") (pintype "passive"))
      (node (ref "Q15") (pin "1") (pinfunction "E_1") (pintype "passive"))
      (node (ref "Q16") (pin "1") (pinfunction "E_1") (pintype "passive"))
      (node (ref "Q2") (pin "1") (pinfunction "E_1") (pintype "passive"))
      (node (ref "Q3") (pin "1") (pinfunction "E_1") (pintype "passive"))
      (node (ref "Q4") (pin "1") (pinfunction "E_1") (pintype "passive"))
      (node (ref "Q5") (pin "1") (pinfunction "E_1") (pintype "passive"))
      (node (ref "Q6") (pin "1") (pinfunction "E_1") (pintype "passive"))
      (node (ref "Q7") (pin "1") (pinfunction "E_1") (pintype "passive"))
      (node (ref "Q8") (pin "1") (pinfunction "E_1") (pintype "passive"))
      (node (ref "Q9") (pin "1") (pinfunction "E_1") (pintype "passive"))
      (node (ref "R24") (pin "2") (pinfunction "2_2") (pintype "passive"))
      (node (ref "U1") (pin "22") (pinfunction "GND_22") (pintype "passive"))
      (node (ref "U1") (pin "8") (pinfunction "GND_8") (pintype "passive"))
      (node (ref "U2") (pin "2") (pinfunction "GND_2") (pintype "passive"))
    )
    (net (code "23") (name "Net-(D1-A)") (class "Default")
      (node (ref "D1") (pin "2") (pinfunction "A_2") (pintype "passive"))
      (node (ref "K1") (pin "11") (pinfunction "11_11") (pintype "passive"))
      (node (ref "Q1") (pin "3") (pinfunction "C_3") (pintype "passive"))
    )
    (net (code "24") (name "Net-(D2-A)") (class "Default")
      (node (ref "D2") (pin "2") (pinfunction "A_2") (pintype "passive"))
      (node (ref "K2") (pin "11") (pinfunction "11_11") (pintype "passive"))
      (node (ref "Q2") (pin "3") (pinfunction "C_3") (pintype "passive"))
    )
    (net (code "25") (name "Net-(D3-A)") (class "Default")
      (node (ref "D3") (pin "2") (pinfunction "A_2") (pintype "passive"))
      (node (ref "K3") (pin "11") (pinfunction "11_11") (pintype "passive"))
      (node (ref "Q3") (pin "3") (pinfunction "C_3") (pintype "passive"))
    )
    (net (code "26") (name "Net-(D4-A)") (class "Default")
      (node (ref "D4") (pin "2") (pinfunction "A_2") (pintype "passive"))
      (node (ref "K4") (pin "11") (pinfunction "11_11") (pintype "passive"))
      (node (ref "Q4") (pin "3") (pinfunction "C_3") (pintype "passive"))
    )
    (net (code "27") (name "Net-(D5-A)") (class "Default")
      (node (ref "D5") (pin "2") (pinfunction "A_2") (pintype "passive"))
      (node (ref "K5") (pin "11") (pinfunction "11_11") (pintype "passive"))
      (node (ref "Q5") (pin "3") (pinfunction "C_3") (pintype "passive"))
    )
    (net (code "28") (name "Net-(D6-A)") (class "Default")
      (node (ref "D6") (pin "2") (pinfunction "A_2") (pintype "passive"))
      (node (ref "K6") (pin "11") (pinfunction "11_11") (pintype "passive"))
      (node (ref "Q6") (pin "3") (pinfunction "C_3") (pintype "passive"))
    )
    (net (code "29") (name "Net-(D7-A)") (class "Default")
      (node (ref "D7") (pin "2") (pinfunction "A_2") (pintype "passive"))
      (node (ref "K7") (pin "11") (pinfunction "11_11") (pintype "passive"))
      (node (ref "Q7") (pin "3") (pinfunction "C_3") (pintype "passive"))
    )
    (net (code "30") (name "Net-(D8-A)") (class "Default")
      (node (ref "D8") (pin "2") (pinfunction "A_2") (pintype "passive"))
      (node (ref "K8") (pin "11") (pinfunction "11_11") (pintype "passive"))
      (node (ref "Q8") (pin "3") (pinfunction "C_3") (pintype "passive"))
    )
    (net (code "31") (name "Net-(D9-A)") (class "Default")
      (node (ref "D9") (pin "2") (pinfunction "A_2") (pintype "passive"))
      (node (ref "K9") (pin "11") (pinfunction "11_11") (pintype "passive"))
      (node (ref "Q9") (pin "3") (pinfunction "C_3") (pintype "passive"))
    )
    (net (code "32") (name "Net-(D10-A)") (class "Default")
      (node (ref "D10") (pin "2") (pinfunction "A_2") (pintype "passive"))
      (node (ref "K10") (pin "11") (pinfunction "11_11") (pintype "passive"))
      (node (ref "Q10") (pin "3") (pinfunction "C_3") (pintype "passive"))
    )
    (net (code "33") (name "Net-(D11-A)") (class "Default")
      (node (ref "D11") (pin "2") (pinfunction "A_2") (pintype "passive"))
      (node (ref "K11") (pin "11") (pinfunction "11_11") (pintype "passive"))
      (node (ref "Q11") (pin "3") (pinfunction "C_3") (pintype "passive"))
    )
    (net (code "34") (name "Net-(D12-A)") (class "Default")
      (node (ref "D12") (pin "2") (pinfunction "A_2") (pintype "passive"))
      (node (ref "K12") (pin "11") (pinfunction "11_11") (pintype "passive"))
      (node (ref "Q12") (pin "3") (pinfunction "C_3") (pintype "passive"))
    )
    (net (code "35") (name "Net-(D13-A)") (class "Default")
      (node (ref "D13") (pin "2") (pinfunction "A_2") (pintype "passive"))
      (node (ref "K13") (pin "11") (pinfunction "11_11") (pintype "passive"))
      (node (ref "Q13") (pin "3") (pinfunction "C_3") (pintype "passive"))
    )
    (net (code "36") (name "Net-(D14-A)") (class "Default")
      (node (ref "D14") (pin "2") (pinfunction "A_2") (pintype "passive"))
      (node (ref "K14") (pin "11") (pinfunction "11_11") (pintype "passive"))
      (node (ref "Q14") (pin "3") (pinfunction "C_3") (pintype "passive"))
    )
    (net (code "37") (name "Net-(D15-A)") (class "Default")
      (node (ref "D15") (pin "2") (pinfunction "A_2") (pintype "passive"))
      (node (ref "K15") (pin "11") (pinfunction "11_11") (pintype "passive"))
      (node (ref "Q15") (pin "3") (pinfunction "C_3") (pintype "passive"))
    )
    (net (code "38") (name "Net-(D16-A)") (class "Default")
      (node (ref "D16") (pin "2") (pinfunction "A_2") (pintype "passive"))
      (node (ref "K16") (pin "11") (pinfunction "11_11") (pintype "passive"))
      (node (ref "Q16") (pin "3") (pinfunction "C_3") (pintype "passive"))
    )
    (net (code "39") (name "Net-(D25-A)") (class "Default")
      (node (ref "D25") (pin "2") (pinfunction "A_2") (pintype "passive"))
      (node (ref "P17") (pin "1") (pinfunction "1_1") (pintype "passive"))
    )
    (net (code "40") (name "Net-(D25-K)") (class "Default")
      (node (ref "C3") (pin "1") (pinfunction "1_1") (pintype "passive"))
      (node (ref "D25") (pin "1") (pinfunction "K_1") (pintype "passive"))
      (node (ref "U2") (pin "1") (pinfunction "IN_1") (pintype "passive"))
    )
    (net (code "41") (name "Net-(J1-Pad3)") (class "Default")
      (node (ref "J1") (pin "3") (pinfunction "3_3") (pintype "passive"))
      (node (ref "J2") (pin "2") (pinfunction "2_2") (pintype "passive"))
    )
    (net (code "42") (name "Net-(K1-Pad1)") (class "Default")
      (node (ref "K1") (pin "1") (pinfunction "1_1") (pintype "passive"))
      (node (ref "P1") (pin "2") (pinfunction "2_2") (pintype "passive"))
    )
    (net (code "43") (name "Net-(K1-Pad12)") (class "Default")
      (node (ref "K1") (pin "12") (pinfunction "12_12") (pintype "passive"))
      (node (ref "P1") (pin "1") (pinfunction "1_1") (pintype "passive"))
    )
    (net (code "44") (name "Net-(K2-Pad1)") (class "Default")
      (node (ref "K2") (pin "1") (pinfunction "1_1") (pintype "passive"))
      (node (ref "P2") (pin "2") (pinfunction "2_2") (pintype "passive"))
    )
    (net (code "45") (name "Net-(K2-Pad12)") (class "Default")
      (node (ref "K2") (pin "12") (pinfunction "12_12") (pintype "passive"))
      (node (ref "P2") (pin "1") (pinfunction "1_1") (pintype "passive"))
    )
    (net (code "46") (name "Net-(K3-Pad1)") (class "Default")
      (node (ref "K3") (pin "1") (pinfunction "1_1") (pintype "passive"))
      (node (ref "P3") (pin "2") (pinfunction "2_2") (pintype "passive"))
    )
    (net (code "47") (name "Net-(K3-Pad12)") (class "Default")
      (node (ref "K3") (pin "12") (pinfunction "12_12") (pintype "passive"))
      (node (ref "P3") (pin "1") (pinfunction "1_1") (pintype "passive"))
    )
    (net (code "48") (name "Net-(K4-Pad1)") (class "Default")
      (node (ref "K4") (pin "1") (pinfunction "1_1") (pintype "passive"))
      (node (ref "P4") (pin "2") (pinfunction "2_2") (pintype "passive"))
    )
    (net (code "49") (name "Net-(K4-Pad12)") (class "Default")
      (node (ref "K4") (pin "12") (pinfunction "12_12") (pintype "passive"))
      (node (ref "P4") (pin "1") (pinfunction "1_1") (pintype "passive"))
    )
    (net (code "50") (name "Net-(K5-Pad1)") (class "Default")
      (node (ref "K5") (pin "1") (pinfunction "1_1") (pintype "passive"))
      (node (ref "P5") (pin "2") (pinfunction "2_2") (pintype "passive"))
    )
    (net (code "51") (name "Net-(K5-Pad12)") (class "Default")
      (node (ref "K5") (pin "12") (pinfunction "12_12") (pintype "passive"))
      (node (ref "P5") (pin "1") (pinfunction "1_1") (pintype "passive"))
    )
    (net (code "52") (name "Net-(K6-Pad1)") (class "Default")
      (node (ref "K6") (pin "1") (pinfunction "1_1") (pintype "passive"))
      (node (ref "P6") (pin "2") (pinfunction "2_2") (pintype "passive"))
    )
    (net (code "53") (name "Net-(K6-Pad12)") (class "Default")
      (node (ref "K6") (pin "12") (pinfunction "12_12") (pintype "passive"))
      (node (ref "P6") (pin "1") (pinfunction "1_1") (pintype "passive"))
    )
    (net (code "54") (name "Net-(K7-Pad1)") (class "Default")
      (node (ref "K7") (pin "1") (pinfunction "1_1") (pintype "passive"))
      (node (ref "P7") (pin "2") (pinfunction "2_2") (pintype "passive"))
    )
    (net (code "55") (name "Net-(K7-Pad12)") (class "Default")
      (node (ref "K7") (pin "12") (pinfunction "12_12") (pintype "passive"))
      (node (ref "P7") (pin "1") (pinfunction "1_1") (pintype "passive"))
    )
    (net (code "56") (name "Net-(K8-Pad1)") (class "Default")
      (node (ref "K8") (pin "1") (pinfunction "1_1") (pintype "passive"))
      (node (ref "P8") (pin "2") (pinfunction "2_2") (pintype "passive"))
    )
    (net (code "57") (name "Net-(K8-Pad12)") (class "Default")
      (node (ref "K8") (pin "12") (pinfunction "12_12") (pintype "passive"))
      (node (ref "P8") (pin "1") (pinfunction "1_1") (pintype "passive"))
    )
    (net (code "58") (name "Net-(K9-Pad1)") (class "Default")
      (node (ref "K9") (pin "1") (pinfunction "1_1") (pintype "passive"))
      (node (ref "P9") (pin "2") (pinfunction "2_2") (pintype "passive"))
    )
    (net (code "59") (name "Net-(K9-Pad12)") (class "Default")
      (node (ref "K9") (pin "12") (pinfunction "12_12") (pintype "passive"))
      (node (ref "P9") (pin "1") (pinfunction "1_1") (pintype "passive"))
    )
    (net (code "60") (name "Net-(K10-Pad1)") (class "Default")
      (node (ref "K10") (pin "1") (pinfunction "1_1") (pintype "passive"))
      (node (ref "P10") (pin "2") (pinfunction "2_2") (pintype "passive"))
    )
    (net (code "61") (name "Net-(K10-Pad12)") (class "Default")
      (node (ref "K10") (pin "12") (pinfunction "12_12") (pintype "passive"))
      (node (ref "P10") (pin "1") (pinfunction "1_1") (pintype "passive"))
    )
    (net (code "62") (name "Net-(K11-Pad1)") (class "Default")
      (node (ref "K11") (pin "1") (pinfunction "1_1") (pintype "passive"))
      (node (ref "P11") (pin "2") (pinfunction "2_2") (pintype "passive"))
    )
    (net (code "63") (name "Net-(K11-Pad12)") (class "Default")
      (node (ref "K11") (pin "12") (pinfunction "12_12") (pintype "passive"))
      (node (ref "P11") (pin "1") (pinfunction "1_1") (pintype "passive"))
    )
    (net (code "64") (name "Net-(K12-Pad1)") (class "Default")
      (node (ref "K12") (pin "1") (pinfunction "1_1") (pintype "passive"))
      (node (ref "P12") (pin "2") (pinfunction "2_2") (pintype "passive"))
    )
    (net (code "65") (name "Net-(K12-Pad12)") (class "Default")
      (node (ref "K12") (pin "12") (pinfunction "12_12") (pintype "passive"))
      (node (ref "P12") (pin "1") (pinfunction "1_1") (pintype "passive"))
    )
    (net (code "66") (name "Net-(K13-Pad1)") (class "Default")
      (node (ref "K13") (pin "1") (pinfunction "1_1") (pintype "passive"))
      (node (ref "P13") (pin "2") (pinfunction "2_2") (pintype "passive"))
    )
    (net (code "67") (name "Net-(K13-Pad12)") (class "Default")
      (node (ref "K13") (pin "12") (pinfunction "12_12") (pintype "passive"))
      (node (ref "P13") (pin "1") (pinfunction "1_1") (pintype "passive"))
    )
    (net (code "68") (name "Net-(K14-Pad1)") (class "Default")
      (node (ref "K14") (pin "1") (pinfunction "1_1") (pintype "passive"))
      (node (ref "P14") (pin "2") (pinfunction "2_2") (pintype "passive"))
    )
    (net (code "69") (name "Net-(K14-Pad12)") (class "Default")
      (node (ref "K14") (pin "12") (pinfunction "12_12") (pintype "passive"))
      (node (ref "P14") (pin "1") (pinfunction "1_1") (pintype "passive"))
    )
    (net (code "70") (name "Net-(K15-Pad1)") (class "Default")
      (node (ref "K15") (pin "1") (pinfunction "1_1") (pintype "passive"))
      (node (ref "P15") (pin "2") (pinfunction "2_2") (pintype "passive"))
    )
    (net (code "71") (name "Net-(K15-Pad12)") (class "Default")
      (node (ref "K15") (pin "12") (pinfunction "12_12") (pintype "passive"))
      (node (ref "P15") (pin "1") (pinfunction "1_1") (pintype "passive"))
    )
    (net (code "72") (name "Net-(K16-Pad1)") (class "Default")
      (node (ref "K16") (pin "1") (pinfunction "1_1") (pintype "passive"))
      (node (ref "P16") (pin "2") (pinfunction "2_2") (pintype "passive"))
    )
    (net (code "73") (name "Net-(K16-Pad12)") (class "Default")
      (node (ref "K16") (pin "12") (pinfunction "12_12") (pintype "passive"))
      (node (ref "P16") (pin "1") (pinfunction "1_1") (pintype "passive"))
    )
    (net (code "74") (name "Net-(LD1-Pad2)") (class "Default")
      (node (ref "LD1") (pin "2") (pinfunction "2_2") (pintype "passive"))
      (node (ref "R24") (pin "1") (pinfunction "1_1") (pintype "passive"))
    )
    (net (code "75") (name "Net-(Q1-B)") (class "Default")
      (node (ref "Q1") (pin "2") (pinfunction "B_2") (pintype "passive"))
      (node (ref "R1") (pin "1") (pinfunction "1_1") (pintype "passive"))
    )
    (net (code "76") (name "Net-(Q2-B)") (class "Default")
      (node (ref "Q2") (pin "2") (pinfunction "B_2") (pintype "passive"))
      (node (ref "R2") (pin "1") (pinfunction "1_1") (pintype "passive"))
    )
    (net (code "77") (name "Net-(Q3-B)") (class "Default")
      (node (ref "Q3") (pin "2") (pinfunction "B_2") (pintype "passive"))
      (node (ref "R3") (pin "1") (pinfunction "1_1") (pintype "passive"))
    )
    (net (code "78") (name "Net-(Q4-B)") (class "Default")
      (node (ref "Q4") (pin "2") (pinfunction "B_2") (pintype "passive"))
      (node (ref "R4") (pin "1") (pinfunction "1_1") (pintype "passive"))
    )
    (net (code "79") (name "Net-(Q5-B)") (class "Default")
      (node (ref "Q5") (pin "2") (pinfunction "B_2") (pintype "passive"))
      (node (ref "R5") (pin "1") (pinfunction "1_1") (pintype "passive"))
    )
    (net (code "80") (name "Net-(Q6-B)") (class "Default")
      (node (ref "Q6") (pin "2") (pinfunction "B_2") (pintype "passive"))
      (node (ref "R6") (pin "1") (pinfunction "1_1") (pintype "passive"))
    )
    (net (code "81") (name "Net-(Q7-B)") (class "Default")
      (node (ref "Q7") (pin "2") (pinfunction "B_2") (pintype "passive"))
      (node (ref "R7") (pin "1") (pinfunction "1_1") (pintype "passive"))
    )
    (net (code "82") (name "Net-(Q8-B)") (class "Default")
      (node (ref "Q8") (pin "2") (pinfunction "B_2") (pintype "passive"))
      (node (ref "R8") (pin "1") (pinfunction "1_1") (pintype "passive"))
    )
    (net (code "83") (name "Net-(Q9-B)") (class "Default")
      (node (ref "Q9") (pin "2") (pinfunction "B_2") (pintype "passive"))
      (node (ref "R9") (pin "1") (pinfunction "1_1") (pintype "passive"))
    )
    (net (code "84") (name "Net-(Q10-B)") (class "Default")
      (node (ref "Q10") (pin "2") (pinfunction "B_2") (pintype "passive"))
      (node (ref "R10") (pin "1") (pinfunction "1_1") (pintype "passive"))
    )
    (net (code "85") (name "Net-(Q11-B)") (class "Default")
      (node (ref "Q11") (pin "2") (pinfunction "B_2") (pintype "passive"))
      (node (ref "R11") (pin "1") (pinfunction "1_1") (pintype "passive"))
    )
    (net (code "86") (name "Net-(Q12-B)") (class "Default")
      (node (ref "Q12") (pin "2") (pinfunction "B_2") (pintype "passive"))
      (node (ref "R12") (pin "1") (pinfunction "1_1") (pintype "passive"))
    )
    (net (code "87") (name "Net-(Q13-B)") (class "Default")
      (node (ref "Q13") (pin "2") (pinfunction "B_2") (pintype "passive"))
      (node (ref "R13") (pin "1") (pinfunction "1_1") (pintype "passive"))
    )
    (net (code "88") (name "Net-(Q14-B)") (class "Default")
      (node (ref "Q14") (pin "2") (pinfunction "B_2") (pintype "passive"))
      (node (ref "R14") (pin "1") (pinfunction "1_1") (pintype "passive"))
    )
    (net (code "89") (name "Net-(Q15-B)") (class "Default")
      (node (ref "Q15") (pin "2") (pinfunction "B_2") (pintype "passive"))
      (node (ref "R15") (pin "1") (pinfunction "1_1") (pintype "passive"))
    )
    (net (code "90") (name "Net-(Q16-B)") (class "Default")
      (node (ref "Q16") (pin "2") (pinfunction "B_2") (pintype "passive"))
      (node (ref "R16") (pin "1") (pinfunction "1_1") (pintype "passive"))
    )
    (net (code "91") (name "Net-(U1-PB6_XTAL1)") (class "Default")
      (node (ref "C1") (pin "2") (pinfunction "2_2") (pintype "passive"))
      (node (ref "U1") (pin "9") (pinfunction "PB6_XTAL1_9") (pintype "passive"))
      (node (ref "X1") (pin "1") (pinfunction "1_1") (pintype "passive"))
    )
    (net (code "92") (name "Net-(U1-PB7_XTAL2)") (class "Default")
      (node (ref "C2") (pin "2") (pinfunction "2_2") (pintype "passive"))
      (node (ref "U1") (pin "10") (pinfunction "PB7_XTAL2_10") (pintype "passive"))
      (node (ref "X1") (pin "2") (pinfunction "2_2") (pintype "passive"))
    )
    (net (code "93") (name "Net-(U1-PC6_RESET#)") (class "Default")
      (node (ref "KEY1") (pin "3") (pinfunction "3_3") (pintype "passive"))
      (node (ref "KEY1") (pin "4") (pinfunction "4_4") (pintype "passive"))
      (node (ref "R25") (pin "1") (pinfunction "1_1") (pintype "passive"))
      (node (ref "U1") (pin "1") (pinfunction "PC6_RESET#_1") (pintype "passive"))
    )
    (net (code "94") (name "Net-(U1-PCINT5_PB5)") (class "Default")
      (node (ref "LD1") (pin "1") (pinfunction "1_1") (pintype "passive"))
      (node (ref "U1") (pin "19") (pinfunction "PCINT5_PB5_19") (pintype "passive"))
    )
    (net (code "95") (name "unconnected-(K1-Pad7)") (class "Default")
      (node (ref "K1") (pin "7") (pinfunction "7_7") (pintype "passive+no_connect"))
    )
    (net (code "96") (name "unconnected-(K2-Pad7)") (class "Default")
      (node (ref "K2") (pin "7") (pinfunction "7_7") (pintype "passive+no_connect"))
    )
    (net (code "97") (name "unconnected-(K3-Pad7)") (class "Default")
      (node (ref "K3") (pin "7") (pinfunction "7_7") (pintype "passive+no_connect"))
    )
    (net (code "98") (name "unconnected-(K4-Pad7)") (class "Default")
      (node (ref "K4") (pin "7") (pinfunction "7_7") (pintype "passive+no_connect"))
    )
    (net (code "99") (name "unconnected-(K5-Pad7)") (class "Default")
      (node (ref "K5") (pin "7") (pinfunction "7_7") (pintype "passive+no_connect"))
    )
    (net (code "100") (name "unconnected-(K6-Pad7)") (class "Default")
      (node (ref "K6") (pin "7") (pinfunction "7_7") (pintype "passive+no_connect"))
    )
    (net (code "101") (name "unconnected-(K7-Pad7)") (class "Default")
      (node (ref "K7") (pin "7") (pinfunction "7_7") (pintype "passive+no_connect"))
    )
    (net (code "102") (name "unconnected-(K8-Pad7)") (class "Default")
      (node (ref "K8") (pin "7") (pinfunction "7_7") (pintype "passive+no_connect"))
    )
    (net (code "103") (name "unconnected-(K9-Pad7)") (class "Default")
      (node (ref "K9") (pin "7") (pinfunction "7_7") (pintype "passive+no_connect"))
    )
    (net (code "104") (name "unconnected-(K10-Pad7)") (class "Default")
      (node (ref "K10") (pin "7") (pinfunction "7_7") (pintype "passive+no_connect"))
    )
    (net (code "105") (name "unconnected-(K11-Pad7)") (class "Default")
      (node (ref "K11") (pin "7") (pinfunction "7_7") (pintype "passive+no_connect"))
    )
    (net (code "106") (name "unconnected-(K12-Pad7)") (class "Default")
      (node (ref "K12") (pin "7") (pinfunction "7_7") (pintype "passive+no_connect"))
    )
    (net (code "107") (name "unconnected-(K13-Pad7)") (class "Default")
      (node (ref "K13") (pin "7") (pinfunction "7_7") (pintype "passive+no_connect"))
    )
    (net (code "108") (name "unconnected-(K14-Pad7)") (class "Default")
      (node (ref "K14") (pin "7") (pinfunction "7_7") (pintype "passive+no_connect"))
    )
    (net (code "109") (name "unconnected-(K15-Pad7)") (class "Default")
      (node (ref "K15") (pin "7") (pinfunction "7_7") (pintype "passive+no_connect"))
    )
    (net (code "110") (name "unconnected-(K16-Pad7)") (class "Default")
      (node (ref "K16") (pin "7") (pinfunction "7_7") (pintype "passive+no_connect"))
    )
    (net (code "111") (name "unconnected-(U1-AREF-Pad21)") (class "Default")
      (node (ref "U1") (pin "21") (pinfunction "AREF_21") (pintype "passive+no_connect"))
    )
    (net (code "112") (name "unconnected-(U1-PD0_RXD-Pad2)") (class "Default")
      (node (ref "U1") (pin "2") (pinfunction "PD0_RXD_2") (pintype "passive+no_connect"))
    )
    (net (code "113") (name "unconnected-(U1-PD1_TXD-Pad3)") (class "Default")
      (node (ref "U1") (pin "3") (pinfunction "PD1_TXD_3") (pintype "passive+no_connect"))
    )
  )
)
